# placa_para_insolar_joystick.net
KiCad netlist of a schematic drawn in EAGLE
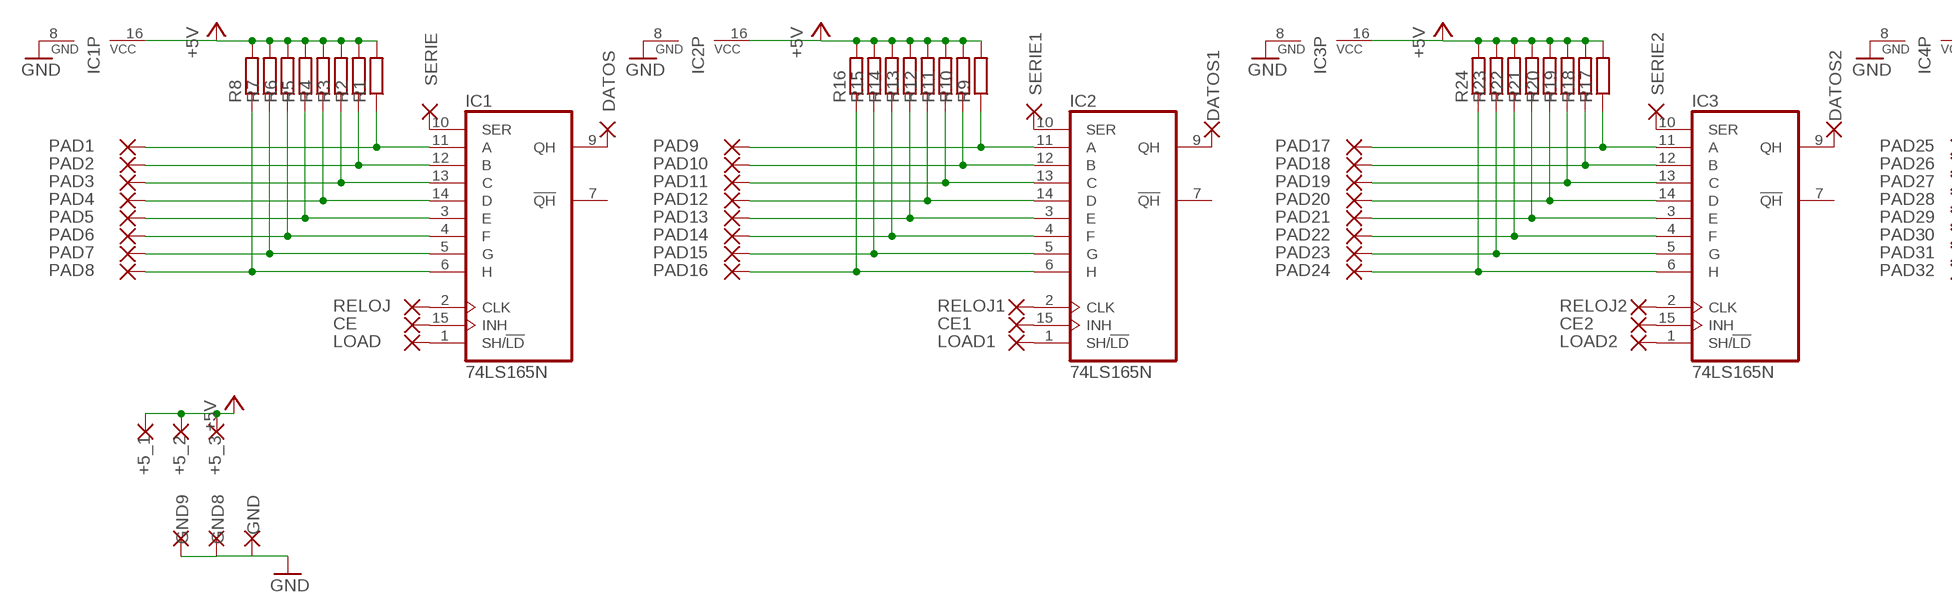
[diagram p0: schematic, sheet 1, part 1 of 2]
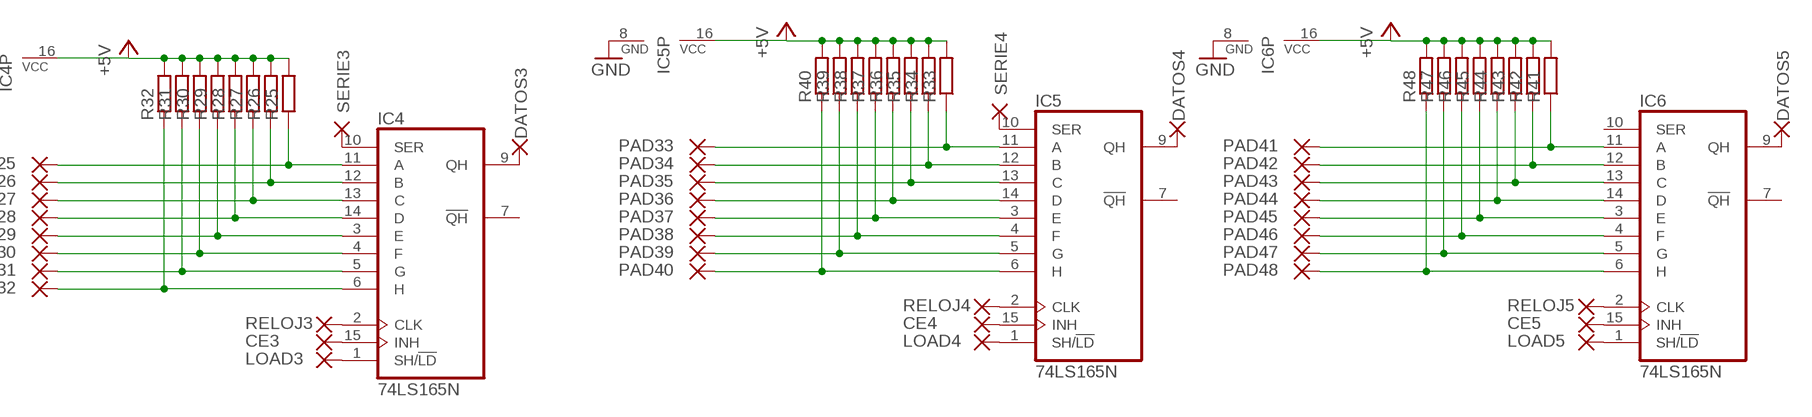
[diagram p1: schematic, sheet 1, part 2 of 2]

(export (version "E")
  (design (tool "Eeschema 10.0.6"))
  (components
    (comp (ref "+5_1")
      (value "WIREPAD2,54/1,0")
      (footprint "eagle-import:2,54_1,0")
      (libsource (lib "eagle-import") (part "WIREPAD2,54/1,0"))
    )
    (comp (ref "+5_2")
      (value "WIREPAD2,54/1,0")
      (footprint "eagle-import:2,54_1,0")
      (libsource (lib "eagle-import") (part "WIREPAD2,54/1,0"))
    )
    (comp (ref "+5_3")
      (value "WIREPAD2,54/1,0")
      (footprint "eagle-import:2,54_1,0")
      (libsource (lib "eagle-import") (part "WIREPAD2,54/1,0"))
    )
    (comp (ref "CE")
      (value "WIREPAD2,54/1,0")
      (footprint "eagle-import:2,54_1,0")
      (libsource (lib "eagle-import") (part "WIREPAD2,54/1,0"))
    )
    (comp (ref "CE1")
      (value "WIREPAD2,54/1,0")
      (footprint "eagle-import:2,54_1,0")
      (libsource (lib "eagle-import") (part "WIREPAD2,54/1,0"))
    )
    (comp (ref "CE2")
      (value "WIREPAD2,54/1,0")
      (footprint "eagle-import:2,54_1,0")
      (libsource (lib "eagle-import") (part "WIREPAD2,54/1,0"))
    )
    (comp (ref "CE3")
      (value "WIREPAD2,54/1,0")
      (footprint "eagle-import:2,54_1,0")
      (libsource (lib "eagle-import") (part "WIREPAD2,54/1,0"))
    )
    (comp (ref "CE4")
      (value "WIREPAD2,54/1,0")
      (footprint "eagle-import:2,54_1,0")
      (libsource (lib "eagle-import") (part "WIREPAD2,54/1,0"))
    )
    (comp (ref "CE5")
      (value "WIREPAD2,54/1,0")
      (footprint "eagle-import:2,54_1,0")
      (libsource (lib "eagle-import") (part "WIREPAD2,54/1,0"))
    )
    (comp (ref "DATOS")
      (value "WIREPAD2,54/1,0")
      (footprint "eagle-import:2,54_1,0")
      (libsource (lib "eagle-import") (part "WIREPAD2,54/1,0"))
    )
    (comp (ref "DATOS1")
      (value "WIREPAD2,54/1,0")
      (footprint "eagle-import:2,54_1,0")
      (libsource (lib "eagle-import") (part "WIREPAD2,54/1,0"))
    )
    (comp (ref "DATOS2")
      (value "WIREPAD2,54/1,0")
      (footprint "eagle-import:2,54_1,0")
      (libsource (lib "eagle-import") (part "WIREPAD2,54/1,0"))
    )
    (comp (ref "DATOS3")
      (value "WIREPAD2,54/1,0")
      (footprint "eagle-import:2,54_1,0")
      (libsource (lib "eagle-import") (part "WIREPAD2,54/1,0"))
    )
    (comp (ref "DATOS4")
      (value "WIREPAD2,54/1,0")
      (footprint "eagle-import:2,54_1,0")
      (libsource (lib "eagle-import") (part "WIREPAD2,54/1,0"))
    )
    (comp (ref "DATOS5")
      (value "WIREPAD2,54/1,0")
      (footprint "eagle-import:2,54_1,0")
      (libsource (lib "eagle-import") (part "WIREPAD2,54/1,0"))
    )
    (comp (ref "GND")
      (value "WIREPAD2,54/1,0")
      (footprint "eagle-import:2,54_1,0")
      (libsource (lib "eagle-import") (part "WIREPAD2,54/1,0"))
    )
    (comp (ref "GND8")
      (value "WIREPAD2,54/1,0")
      (footprint "eagle-import:2,54_1,0")
      (libsource (lib "eagle-import") (part "WIREPAD2,54/1,0"))
    )
    (comp (ref "GND9")
      (value "WIREPAD2,54/1,0")
      (footprint "eagle-import:2,54_1,0")
      (libsource (lib "eagle-import") (part "WIREPAD2,54/1,0"))
    )
    (comp (ref "IC1")
      (value "74LS165N")
      (footprint "eagle-import:DIL16")
      (libsource (lib "eagle-import") (part "74165NLS"))
    )
    (comp (ref "IC2")
      (value "74LS165N")
      (footprint "eagle-import:DIL16")
      (libsource (lib "eagle-import") (part "74165NLS"))
    )
    (comp (ref "IC3")
      (value "74LS165N")
      (footprint "eagle-import:DIL16")
      (libsource (lib "eagle-import") (part "74165NLS"))
    )
    (comp (ref "IC4")
      (value "74LS165N")
      (footprint "eagle-import:DIL16")
      (libsource (lib "eagle-import") (part "74165NLS"))
    )
    (comp (ref "IC5")
      (value "74LS165N")
      (footprint "eagle-import:DIL16")
      (libsource (lib "eagle-import") (part "74165NLS"))
    )
    (comp (ref "IC6")
      (value "74LS165N")
      (footprint "eagle-import:DIL16")
      (libsource (lib "eagle-import") (part "74165NLS"))
    )
    (comp (ref "LOAD")
      (value "WIREPAD2,54/1,0")
      (footprint "eagle-import:2,54_1,0")
      (libsource (lib "eagle-import") (part "WIREPAD2,54/1,0"))
    )
    (comp (ref "LOAD1")
      (value "WIREPAD2,54/1,0")
      (footprint "eagle-import:2,54_1,0")
      (libsource (lib "eagle-import") (part "WIREPAD2,54/1,0"))
    )
    (comp (ref "LOAD2")
      (value "WIREPAD2,54/1,0")
      (footprint "eagle-import:2,54_1,0")
      (libsource (lib "eagle-import") (part "WIREPAD2,54/1,0"))
    )
    (comp (ref "LOAD3")
      (value "WIREPAD2,54/1,0")
      (footprint "eagle-import:2,54_1,0")
      (libsource (lib "eagle-import") (part "WIREPAD2,54/1,0"))
    )
    (comp (ref "LOAD4")
      (value "WIREPAD2,54/1,0")
      (footprint "eagle-import:2,54_1,0")
      (libsource (lib "eagle-import") (part "WIREPAD2,54/1,0"))
    )
    (comp (ref "LOAD5")
      (value "WIREPAD2,54/1,0")
      (footprint "eagle-import:2,54_1,0")
      (libsource (lib "eagle-import") (part "WIREPAD2,54/1,0"))
    )
    (comp (ref "PAD1")
      (value "WIREPAD2,54/1,0")
      (footprint "eagle-import:2,54_1,0")
      (libsource (lib "eagle-import") (part "WIREPAD2,54/1,0"))
    )
    (comp (ref "PAD2")
      (value "WIREPAD2,54/1,0")
      (footprint "eagle-import:2,54_1,0")
      (libsource (lib "eagle-import") (part "WIREPAD2,54/1,0"))
    )
    (comp (ref "PAD3")
      (value "WIREPAD2,54/1,0")
      (footprint "eagle-import:2,54_1,0")
      (libsource (lib "eagle-import") (part "WIREPAD2,54/1,0"))
    )
    (comp (ref "PAD4")
      (value "WIREPAD2,54/1,0")
      (footprint "eagle-import:2,54_1,0")
      (libsource (lib "eagle-import") (part "WIREPAD2,54/1,0"))
    )
    (comp (ref "PAD5")
      (value "WIREPAD2,54/1,0")
      (footprint "eagle-import:2,54_1,0")
      (libsource (lib "eagle-import") (part "WIREPAD2,54/1,0"))
    )
    (comp (ref "PAD6")
      (value "WIREPAD2,54/1,0")
      (footprint "eagle-import:2,54_1,0")
      (libsource (lib "eagle-import") (part "WIREPAD2,54/1,0"))
    )
    (comp (ref "PAD7")
      (value "WIREPAD2,54/1,0")
      (footprint "eagle-import:2,54_1,0")
      (libsource (lib "eagle-import") (part "WIREPAD2,54/1,0"))
    )
    (comp (ref "PAD8")
      (value "WIREPAD2,54/1,0")
      (footprint "eagle-import:2,54_1,0")
      (libsource (lib "eagle-import") (part "WIREPAD2,54/1,0"))
    )
    (comp (ref "PAD9")
      (value "WIREPAD2,54/1,0")
      (footprint "eagle-import:2,54_1,0")
      (libsource (lib "eagle-import") (part "WIREPAD2,54/1,0"))
    )
    (comp (ref "PAD10")
      (value "WIREPAD2,54/1,0")
      (footprint "eagle-import:2,54_1,0")
      (libsource (lib "eagle-import") (part "WIREPAD2,54/1,0"))
    )
    (comp (ref "PAD11")
      (value "WIREPAD2,54/1,0")
      (footprint "eagle-import:2,54_1,0")
      (libsource (lib "eagle-import") (part "WIREPAD2,54/1,0"))
    )
    (comp (ref "PAD12")
      (value "WIREPAD2,54/1,0")
      (footprint "eagle-import:2,54_1,0")
      (libsource (lib "eagle-import") (part "WIREPAD2,54/1,0"))
    )
    (comp (ref "PAD13")
      (value "WIREPAD2,54/1,0")
      (footprint "eagle-import:2,54_1,0")
      (libsource (lib "eagle-import") (part "WIREPAD2,54/1,0"))
    )
    (comp (ref "PAD14")
      (value "WIREPAD2,54/1,0")
      (footprint "eagle-import:2,54_1,0")
      (libsource (lib "eagle-import") (part "WIREPAD2,54/1,0"))
    )
    (comp (ref "PAD15")
      (value "WIREPAD2,54/1,0")
      (footprint "eagle-import:2,54_1,0")
      (libsource (lib "eagle-import") (part "WIREPAD2,54/1,0"))
    )
    (comp (ref "PAD16")
      (value "WIREPAD2,54/1,0")
      (footprint "eagle-import:2,54_1,0")
      (libsource (lib "eagle-import") (part "WIREPAD2,54/1,0"))
    )
    (comp (ref "PAD17")
      (value "WIREPAD2,54/1,0")
      (footprint "eagle-import:2,54_1,0")
      (libsource (lib "eagle-import") (part "WIREPAD2,54/1,0"))
    )
    (comp (ref "PAD18")
      (value "WIREPAD2,54/1,0")
      (footprint "eagle-import:2,54_1,0")
      (libsource (lib "eagle-import") (part "WIREPAD2,54/1,0"))
    )
    (comp (ref "PAD19")
      (value "WIREPAD2,54/1,0")
      (footprint "eagle-import:2,54_1,0")
      (libsource (lib "eagle-import") (part "WIREPAD2,54/1,0"))
    )
    (comp (ref "PAD20")
      (value "WIREPAD2,54/1,0")
      (footprint "eagle-import:2,54_1,0")
      (libsource (lib "eagle-import") (part "WIREPAD2,54/1,0"))
    )
    (comp (ref "PAD21")
      (value "WIREPAD2,54/1,0")
      (footprint "eagle-import:2,54_1,0")
      (libsource (lib "eagle-import") (part "WIREPAD2,54/1,0"))
    )
    (comp (ref "PAD22")
      (value "WIREPAD2,54/1,0")
      (footprint "eagle-import:2,54_1,0")
      (libsource (lib "eagle-import") (part "WIREPAD2,54/1,0"))
    )
    (comp (ref "PAD23")
      (value "WIREPAD2,54/1,0")
      (footprint "eagle-import:2,54_1,0")
      (libsource (lib "eagle-import") (part "WIREPAD2,54/1,0"))
    )
    (comp (ref "PAD24")
      (value "WIREPAD2,54/1,0")
      (footprint "eagle-import:2,54_1,0")
      (libsource (lib "eagle-import") (part "WIREPAD2,54/1,0"))
    )
    (comp (ref "PAD25")
      (value "WIREPAD2,54/1,0")
      (footprint "eagle-import:2,54_1,0")
      (libsource (lib "eagle-import") (part "WIREPAD2,54/1,0"))
    )
    (comp (ref "PAD26")
      (value "WIREPAD2,54/1,0")
      (footprint "eagle-import:2,54_1,0")
      (libsource (lib "eagle-import") (part "WIREPAD2,54/1,0"))
    )
    (comp (ref "PAD27")
      (value "WIREPAD2,54/1,0")
      (footprint "eagle-import:2,54_1,0")
      (libsource (lib "eagle-import") (part "WIREPAD2,54/1,0"))
    )
    (comp (ref "PAD28")
      (value "WIREPAD2,54/1,0")
      (footprint "eagle-import:2,54_1,0")
      (libsource (lib "eagle-import") (part "WIREPAD2,54/1,0"))
    )
    (comp (ref "PAD29")
      (value "WIREPAD2,54/1,0")
      (footprint "eagle-import:2,54_1,0")
      (libsource (lib "eagle-import") (part "WIREPAD2,54/1,0"))
    )
    (comp (ref "PAD30")
      (value "WIREPAD2,54/1,0")
      (footprint "eagle-import:2,54_1,0")
      (libsource (lib "eagle-import") (part "WIREPAD2,54/1,0"))
    )
    (comp (ref "PAD31")
      (value "WIREPAD2,54/1,0")
      (footprint "eagle-import:2,54_1,0")
      (libsource (lib "eagle-import") (part "WIREPAD2,54/1,0"))
    )
    (comp (ref "PAD32")
      (value "WIREPAD2,54/1,0")
      (footprint "eagle-import:2,54_1,0")
      (libsource (lib "eagle-import") (part "WIREPAD2,54/1,0"))
    )
    (comp (ref "PAD33")
      (value "WIREPAD2,54/1,0")
      (footprint "eagle-import:2,54_1,0")
      (libsource (lib "eagle-import") (part "WIREPAD2,54/1,0"))
    )
    (comp (ref "PAD34")
      (value "WIREPAD2,54/1,0")
      (footprint "eagle-import:2,54_1,0")
      (libsource (lib "eagle-import") (part "WIREPAD2,54/1,0"))
    )
    (comp (ref "PAD35")
      (value "WIREPAD2,54/1,0")
      (footprint "eagle-import:2,54_1,0")
      (libsource (lib "eagle-import") (part "WIREPAD2,54/1,0"))
    )
    (comp (ref "PAD36")
      (value "WIREPAD2,54/1,0")
      (footprint "eagle-import:2,54_1,0")
      (libsource (lib "eagle-import") (part "WIREPAD2,54/1,0"))
    )
    (comp (ref "PAD37")
      (value "WIREPAD2,54/1,0")
      (footprint "eagle-import:2,54_1,0")
      (libsource (lib "eagle-import") (part "WIREPAD2,54/1,0"))
    )
    (comp (ref "PAD38")
      (value "WIREPAD2,54/1,0")
      (footprint "eagle-import:2,54_1,0")
      (libsource (lib "eagle-import") (part "WIREPAD2,54/1,0"))
    )
    (comp (ref "PAD39")
      (value "WIREPAD2,54/1,0")
      (footprint "eagle-import:2,54_1,0")
      (libsource (lib "eagle-import") (part "WIREPAD2,54/1,0"))
    )
    (comp (ref "PAD40")
      (value "WIREPAD2,54/1,0")
      (footprint "eagle-import:2,54_1,0")
      (libsource (lib "eagle-import") (part "WIREPAD2,54/1,0"))
    )
    (comp (ref "PAD41")
      (value "WIREPAD2,54/1,0")
      (footprint "eagle-import:2,54_1,0")
      (libsource (lib "eagle-import") (part "WIREPAD2,54/1,0"))
    )
    (comp (ref "PAD42")
      (value "WIREPAD2,54/1,0")
      (footprint "eagle-import:2,54_1,0")
      (libsource (lib "eagle-import") (part "WIREPAD2,54/1,0"))
    )
    (comp (ref "PAD43")
      (value "WIREPAD2,54/1,0")
      (footprint "eagle-import:2,54_1,0")
      (libsource (lib "eagle-import") (part "WIREPAD2,54/1,0"))
    )
    (comp (ref "PAD44")
      (value "WIREPAD2,54/1,0")
      (footprint "eagle-import:2,54_1,0")
      (libsource (lib "eagle-import") (part "WIREPAD2,54/1,0"))
    )
    (comp (ref "PAD45")
      (value "WIREPAD2,54/1,0")
      (footprint "eagle-import:2,54_1,0")
      (libsource (lib "eagle-import") (part "WIREPAD2,54/1,0"))
    )
    (comp (ref "PAD46")
      (value "WIREPAD2,54/1,0")
      (footprint "eagle-import:2,54_1,0")
      (libsource (lib "eagle-import") (part "WIREPAD2,54/1,0"))
    )
    (comp (ref "PAD47")
      (value "WIREPAD2,54/1,0")
      (footprint "eagle-import:2,54_1,0")
      (libsource (lib "eagle-import") (part "WIREPAD2,54/1,0"))
    )
    (comp (ref "PAD48")
      (value "WIREPAD2,54/1,0")
      (footprint "eagle-import:2,54_1,0")
      (libsource (lib "eagle-import") (part "WIREPAD2,54/1,0"))
    )
    (comp (ref "R1")
      (value "R-EU_0204/7")
      (footprint "eagle-import:0204_7")
      (libsource (lib "eagle-import") (part "R-EU_0204/7"))
    )
    (comp (ref "R2")
      (value "R-EU_0204/7")
      (footprint "eagle-import:0204_7")
      (libsource (lib "eagle-import") (part "R-EU_0204/7"))
    )
    (comp (ref "R3")
      (value "R-EU_0204/7")
      (footprint "eagle-import:0204_7")
      (libsource (lib "eagle-import") (part "R-EU_0204/7"))
    )
    (comp (ref "R4")
      (value "R-EU_0204/7")
      (footprint "eagle-import:0204_7")
      (libsource (lib "eagle-import") (part "R-EU_0204/7"))
    )
    (comp (ref "R5")
      (value "R-EU_0204/7")
      (footprint "eagle-import:0204_7")
      (libsource (lib "eagle-import") (part "R-EU_0204/7"))
    )
    (comp (ref "R6")
      (value "R-EU_0204/7")
      (footprint "eagle-import:0204_7")
      (libsource (lib "eagle-import") (part "R-EU_0204/7"))
    )
    (comp (ref "R7")
      (value "R-EU_0204/7")
      (footprint "eagle-import:0204_7")
      (libsource (lib "eagle-import") (part "R-EU_0204/7"))
    )
    (comp (ref "R8")
      (value "R-EU_0204/7")
      (footprint "eagle-import:0204_7")
      (libsource (lib "eagle-import") (part "R-EU_0204/7"))
    )
    (comp (ref "R9")
      (value "R-EU_0204/7")
      (footprint "eagle-import:0204_7")
      (libsource (lib "eagle-import") (part "R-EU_0204/7"))
    )
    (comp (ref "R10")
      (value "R-EU_0204/7")
      (footprint "eagle-import:0204_7")
      (libsource (lib "eagle-import") (part "R-EU_0204/7"))
    )
    (comp (ref "R11")
      (value "R-EU_0204/7")
      (footprint "eagle-import:0204_7")
      (libsource (lib "eagle-import") (part "R-EU_0204/7"))
    )
    (comp (ref "R12")
      (value "R-EU_0204/7")
      (footprint "eagle-import:0204_7")
      (libsource (lib "eagle-import") (part "R-EU_0204/7"))
    )
    (comp (ref "R13")
      (value "R-EU_0204/7")
      (footprint "eagle-import:0204_7")
      (libsource (lib "eagle-import") (part "R-EU_0204/7"))
    )
    (comp (ref "R14")
      (value "R-EU_0204/7")
      (footprint "eagle-import:0204_7")
      (libsource (lib "eagle-import") (part "R-EU_0204/7"))
    )
    (comp (ref "R15")
      (value "R-EU_0204/7")
      (footprint "eagle-import:0204_7")
      (libsource (lib "eagle-import") (part "R-EU_0204/7"))
    )
    (comp (ref "R16")
      (value "R-EU_0204/7")
      (footprint "eagle-import:0204_7")
      (libsource (lib "eagle-import") (part "R-EU_0204/7"))
    )
    (comp (ref "R17")
      (value "R-EU_0204/7")
      (footprint "eagle-import:0204_7")
      (libsource (lib "eagle-import") (part "R-EU_0204/7"))
    )
    (comp (ref "R18")
      (value "R-EU_0204/7")
      (footprint "eagle-import:0204_7")
      (libsource (lib "eagle-import") (part "R-EU_0204/7"))
    )
    (comp (ref "R19")
      (value "R-EU_0204/7")
      (footprint "eagle-import:0204_7")
      (libsource (lib "eagle-import") (part "R-EU_0204/7"))
    )
    (comp (ref "R20")
      (value "R-EU_0204/7")
      (footprint "eagle-import:0204_7")
      (libsource (lib "eagle-import") (part "R-EU_0204/7"))
    )
    (comp (ref "R21")
      (value "R-EU_0204/7")
      (footprint "eagle-import:0204_7")
      (libsource (lib "eagle-import") (part "R-EU_0204/7"))
    )
    (comp (ref "R22")
      (value "R-EU_0204/7")
      (footprint "eagle-import:0204_7")
      (libsource (lib "eagle-import") (part "R-EU_0204/7"))
    )
    (comp (ref "R23")
      (value "R-EU_0204/7")
      (footprint "eagle-import:0204_7")
      (libsource (lib "eagle-import") (part "R-EU_0204/7"))
    )
    (comp (ref "R24")
      (value "R-EU_0204/7")
      (footprint "eagle-import:0204_7")
      (libsource (lib "eagle-import") (part "R-EU_0204/7"))
    )
    (comp (ref "R25")
      (value "R-EU_0204/7")
      (footprint "eagle-import:0204_7")
      (libsource (lib "eagle-import") (part "R-EU_0204/7"))
    )
    (comp (ref "R26")
      (value "R-EU_0204/7")
      (footprint "eagle-import:0204_7")
      (libsource (lib "eagle-import") (part "R-EU_0204/7"))
    )
    (comp (ref "R27")
      (value "R-EU_0204/7")
      (footprint "eagle-import:0204_7")
      (libsource (lib "eagle-import") (part "R-EU_0204/7"))
    )
    (comp (ref "R28")
      (value "R-EU_0204/7")
      (footprint "eagle-import:0204_7")
      (libsource (lib "eagle-import") (part "R-EU_0204/7"))
    )
    (comp (ref "R29")
      (value "R-EU_0204/7")
      (footprint "eagle-import:0204_7")
      (libsource (lib "eagle-import") (part "R-EU_0204/7"))
    )
    (comp (ref "R30")
      (value "R-EU_0204/7")
      (footprint "eagle-import:0204_7")
      (libsource (lib "eagle-import") (part "R-EU_0204/7"))
    )
    (comp (ref "R31")
      (value "R-EU_0204/7")
      (footprint "eagle-import:0204_7")
      (libsource (lib "eagle-import") (part "R-EU_0204/7"))
    )
    (comp (ref "R32")
      (value "R-EU_0204/7")
      (footprint "eagle-import:0204_7")
      (libsource (lib "eagle-import") (part "R-EU_0204/7"))
    )
    (comp (ref "R33")
      (value "R-EU_0204/7")
      (footprint "eagle-import:0204_7")
      (libsource (lib "eagle-import") (part "R-EU_0204/7"))
    )
    (comp (ref "R34")
      (value "R-EU_0204/7")
      (footprint "eagle-import:0204_7")
      (libsource (lib "eagle-import") (part "R-EU_0204/7"))
    )
    (comp (ref "R35")
      (value "R-EU_0204/7")
      (footprint "eagle-import:0204_7")
      (libsource (lib "eagle-import") (part "R-EU_0204/7"))
    )
    (comp (ref "R36")
      (value "R-EU_0204/7")
      (footprint "eagle-import:0204_7")
      (libsource (lib "eagle-import") (part "R-EU_0204/7"))
    )
    (comp (ref "R37")
      (value "R-EU_0204/7")
      (footprint "eagle-import:0204_7")
      (libsource (lib "eagle-import") (part "R-EU_0204/7"))
    )
    (comp (ref "R38")
      (value "R-EU_0204/7")
      (footprint "eagle-import:0204_7")
      (libsource (lib "eagle-import") (part "R-EU_0204/7"))
    )
    (comp (ref "R39")
      (value "R-EU_0204/7")
      (footprint "eagle-import:0204_7")
      (libsource (lib "eagle-import") (part "R-EU_0204/7"))
    )
    (comp (ref "R40")
      (value "R-EU_0204/7")
      (footprint "eagle-import:0204_7")
      (libsource (lib "eagle-import") (part "R-EU_0204/7"))
    )
    (comp (ref "R41")
      (value "R-EU_0204/7")
      (footprint "eagle-import:0204_7")
      (libsource (lib "eagle-import") (part "R-EU_0204/7"))
    )
    (comp (ref "R42")
      (value "R-EU_0204/7")
      (footprint "eagle-import:0204_7")
      (libsource (lib "eagle-import") (part "R-EU_0204/7"))
    )
    (comp (ref "R43")
      (value "R-EU_0204/7")
      (footprint "eagle-import:0204_7")
      (libsource (lib "eagle-import") (part "R-EU_0204/7"))
    )
    (comp (ref "R44")
      (value "R-EU_0204/7")
      (footprint "eagle-import:0204_7")
      (libsource (lib "eagle-import") (part "R-EU_0204/7"))
    )
    (comp (ref "R45")
      (value "R-EU_0204/7")
      (footprint "eagle-import:0204_7")
      (libsource (lib "eagle-import") (part "R-EU_0204/7"))
    )
    (comp (ref "R46")
      (value "R-EU_0204/7")
      (footprint "eagle-import:0204_7")
      (libsource (lib "eagle-import") (part "R-EU_0204/7"))
    )
    (comp (ref "R47")
      (value "R-EU_0204/7")
      (footprint "eagle-import:0204_7")
      (libsource (lib "eagle-import") (part "R-EU_0204/7"))
    )
    (comp (ref "R48")
      (value "R-EU_0204/7")
      (footprint "eagle-import:0204_7")
      (libsource (lib "eagle-import") (part "R-EU_0204/7"))
    )
    (comp (ref "RELOJ")
      (value "WIREPAD2,54/1,0")
      (footprint "eagle-import:2,54_1,0")
      (libsource (lib "eagle-import") (part "WIREPAD2,54/1,0"))
    )
    (comp (ref "RELOJ1")
      (value "WIREPAD2,54/1,0")
      (footprint "eagle-import:2,54_1,0")
      (libsource (lib "eagle-import") (part "WIREPAD2,54/1,0"))
    )
    (comp (ref "RELOJ2")
      (value "WIREPAD2,54/1,0")
      (footprint "eagle-import:2,54_1,0")
      (libsource (lib "eagle-import") (part "WIREPAD2,54/1,0"))
    )
    (comp (ref "RELOJ3")
      (value "WIREPAD2,54/1,0")
      (footprint "eagle-import:2,54_1,0")
      (libsource (lib "eagle-import") (part "WIREPAD2,54/1,0"))
    )
    (comp (ref "RELOJ4")
      (value "WIREPAD2,54/1,0")
      (footprint "eagle-import:2,54_1,0")
      (libsource (lib "eagle-import") (part "WIREPAD2,54/1,0"))
    )
    (comp (ref "RELOJ5")
      (value "WIREPAD2,54/1,0")
      (footprint "eagle-import:2,54_1,0")
      (libsource (lib "eagle-import") (part "WIREPAD2,54/1,0"))
    )
    (comp (ref "SERIE")
      (value "WIREPAD2,54/1,0")
      (footprint "eagle-import:2,54_1,0")
      (libsource (lib "eagle-import") (part "WIREPAD2,54/1,0"))
    )
    (comp (ref "SERIE1")
      (value "WIREPAD2,54/1,0")
      (footprint "eagle-import:2,54_1,0")
      (libsource (lib "eagle-import") (part "WIREPAD2,54/1,0"))
    )
    (comp (ref "SERIE2")
      (value "WIREPAD2,54/1,0")
      (footprint "eagle-import:2,54_1,0")
      (libsource (lib "eagle-import") (part "WIREPAD2,54/1,0"))
    )
    (comp (ref "SERIE3")
      (value "WIREPAD2,54/1,0")
      (footprint "eagle-import:2,54_1,0")
      (libsource (lib "eagle-import") (part "WIREPAD2,54/1,0"))
    )
    (comp (ref "SERIE4")
      (value "WIREPAD2,54/1,0")
      (footprint "eagle-import:2,54_1,0")
      (libsource (lib "eagle-import") (part "WIREPAD2,54/1,0"))
    )
  )
  (nets
    (net (code "1") (name "+5V") (class "Default")
      (node (ref "+5_1") (pin "1") (pinfunction "P_1") (pintype "passive"))
      (node (ref "+5_2") (pin "1") (pinfunction "P_1") (pintype "passive"))
      (node (ref "+5_3") (pin "1") (pinfunction "P_1") (pintype "passive"))
      (node (ref "IC1") (pin "16") (pinfunction "VCC_16") (pintype "power_in"))
      (node (ref "IC2") (pin "16") (pinfunction "VCC_16") (pintype "power_in"))
      (node (ref "IC3") (pin "16") (pinfunction "VCC_16") (pintype "power_in"))
      (node (ref "IC4") (pin "16") (pinfunction "VCC_16") (pintype "power_in"))
      (node (ref "IC5") (pin "16") (pinfunction "VCC_16") (pintype "power_in"))
      (node (ref "IC6") (pin "16") (pinfunction "VCC_16") (pintype "power_in"))
      (node (ref "R1") (pin "2") (pinfunction "2_2") (pintype "passive"))
      (node (ref "R10") (pin "2") (pinfunction "2_2") (pintype "passive"))
      (node (ref "R11") (pin "2") (pinfunction "2_2") (pintype "passive"))
      (node (ref "R12") (pin "2") (pinfunction "2_2") (pintype "passive"))
      (node (ref "R13") (pin "2") (pinfunction "2_2") (pintype "passive"))
      (node (ref "R14") (pin "2") (pinfunction "2_2") (pintype "passive"))
      (node (ref "R15") (pin "2") (pinfunction "2_2") (pintype "passive"))
      (node (ref "R16") (pin "2") (pinfunction "2_2") (pintype "passive"))
      (node (ref "R17") (pin "2") (pinfunction "2_2") (pintype "passive"))
      (node (ref "R18") (pin "2") (pinfunction "2_2") (pintype "passive"))
      (node (ref "R19") (pin "2") (pinfunction "2_2") (pintype "passive"))
      (node (ref "R2") (pin "2") (pinfunction "2_2") (pintype "passive"))
      (node (ref "R20") (pin "2") (pinfunction "2_2") (pintype "passive"))
      (node (ref "R21") (pin "2") (pinfunction "2_2") (pintype "passive"))
      (node (ref "R22") (pin "2") (pinfunction "2_2") (pintype "passive"))
      (node (ref "R23") (pin "2") (pinfunction "2_2") (pintype "passive"))
      (node (ref "R24") (pin "2") (pinfunction "2_2") (pintype "passive"))
      (node (ref "R25") (pin "2") (pinfunction "2_2") (pintype "passive"))
      (node (ref "R26") (pin "2") (pinfunction "2_2") (pintype "passive"))
      (node (ref "R27") (pin "2") (pinfunction "2_2") (pintype "passive"))
      (node (ref "R28") (pin "2") (pinfunction "2_2") (pintype "passive"))
      (node (ref "R29") (pin "2") (pinfunction "2_2") (pintype "passive"))
      (node (ref "R3") (pin "2") (pinfunction "2_2") (pintype "passive"))
      (node (ref "R30") (pin "2") (pinfunction "2_2") (pintype "passive"))
      (node (ref "R31") (pin "2") (pinfunction "2_2") (pintype "passive"))
      (node (ref "R32") (pin "2") (pinfunction "2_2") (pintype "passive"))
      (node (ref "R33") (pin "2") (pinfunction "2_2") (pintype "passive"))
      (node (ref "R34") (pin "2") (pinfunction "2_2") (pintype "passive"))
      (node (ref "R35") (pin "2") (pinfunction "2_2") (pintype "passive"))
      (node (ref "R36") (pin "2") (pinfunction "2_2") (pintype "passive"))
      (node (ref "R37") (pin "2") (pinfunction "2_2") (pintype "passive"))
      (node (ref "R38") (pin "2") (pinfunction "2_2") (pintype "passive"))
      (node (ref "R39") (pin "2") (pinfunction "2_2") (pintype "passive"))
      (node (ref "R4") (pin "2") (pinfunction "2_2") (pintype "passive"))
      (node (ref "R40") (pin "2") (pinfunction "2_2") (pintype "passive"))
      (node (ref "R41") (pin "2") (pinfunction "2_2") (pintype "passive"))
      (node (ref "R42") (pin "2") (pinfunction "2_2") (pintype "passive"))
      (node (ref "R43") (pin "2") (pinfunction "2_2") (pintype "passive"))
      (node (ref "R44") (pin "2") (pinfunction "2_2") (pintype "passive"))
      (node (ref "R45") (pin "2") (pinfunction "2_2") (pintype "passive"))
      (node (ref "R46") (pin "2") (pinfunction "2_2") (pintype "passive"))
      (node (ref "R47") (pin "2") (pinfunction "2_2") (pintype "passive"))
      (node (ref "R48") (pin "2") (pinfunction "2_2") (pintype "passive"))
      (node (ref "R5") (pin "2") (pinfunction "2_2") (pintype "passive"))
      (node (ref "R6") (pin "2") (pinfunction "2_2") (pintype "passive"))
      (node (ref "R7") (pin "2") (pinfunction "2_2") (pintype "passive"))
      (node (ref "R8") (pin "2") (pinfunction "2_2") (pintype "passive"))
      (node (ref "R9") (pin "2") (pinfunction "2_2") (pintype "passive"))
    )
    (net (code "2") (name "GND") (class "Default")
      (node (ref "GND") (pin "1") (pinfunction "P_1") (pintype "passive"))
      (node (ref "GND8") (pin "1") (pinfunction "P_1") (pintype "passive"))
      (node (ref "GND9") (pin "1") (pinfunction "P_1") (pintype "passive"))
      (node (ref "IC1") (pin "8") (pinfunction "GND_8") (pintype "power_in"))
      (node (ref "IC2") (pin "8") (pinfunction "GND_8") (pintype "power_in"))
      (node (ref "IC3") (pin "8") (pinfunction "GND_8") (pintype "power_in"))
      (node (ref "IC4") (pin "8") (pinfunction "GND_8") (pintype "power_in"))
      (node (ref "IC5") (pin "8") (pinfunction "GND_8") (pintype "power_in"))
      (node (ref "IC6") (pin "8") (pinfunction "GND_8") (pintype "power_in"))
    )
    (net (code "3") (name "Net-(CE-P)") (class "Default")
      (node (ref "CE") (pin "1") (pinfunction "P_1") (pintype "passive"))
      (node (ref "IC1") (pin "15") (pinfunction "INH_15") (pintype "input"))
    )
    (net (code "4") (name "Net-(CE1-P)") (class "Default")
      (node (ref "CE1") (pin "1") (pinfunction "P_1") (pintype "passive"))
      (node (ref "IC2") (pin "15") (pinfunction "INH_15") (pintype "input"))
    )
    (net (code "5") (name "Net-(CE2-P)") (class "Default")
      (node (ref "CE2") (pin "1") (pinfunction "P_1") (pintype "passive"))
      (node (ref "IC3") (pin "15") (pinfunction "INH_15") (pintype "input"))
    )
    (net (code "6") (name "Net-(CE3-P)") (class "Default")
      (node (ref "CE3") (pin "1") (pinfunction "P_1") (pintype "passive"))
      (node (ref "IC4") (pin "15") (pinfunction "INH_15") (pintype "input"))
    )
    (net (code "7") (name "Net-(CE4-P)") (class "Default")
      (node (ref "CE4") (pin "1") (pinfunction "P_1") (pintype "passive"))
      (node (ref "IC5") (pin "15") (pinfunction "INH_15") (pintype "input"))
    )
    (net (code "8") (name "Net-(CE5-P)") (class "Default")
      (node (ref "CE5") (pin "1") (pinfunction "P_1") (pintype "passive"))
      (node (ref "IC6") (pin "15") (pinfunction "INH_15") (pintype "input"))
    )
    (net (code "9") (name "Net-(DATOS-P)") (class "Default")
      (node (ref "DATOS") (pin "1") (pinfunction "P_1") (pintype "passive"))
      (node (ref "IC1") (pin "9") (pinfunction "QH_9") (pintype "output"))
    )
    (net (code "10") (name "Net-(DATOS1-P)") (class "Default")
      (node (ref "DATOS1") (pin "1") (pinfunction "P_1") (pintype "passive"))
      (node (ref "IC2") (pin "9") (pinfunction "QH_9") (pintype "output"))
    )
    (net (code "11") (name "Net-(DATOS2-P)") (class "Default")
      (node (ref "DATOS2") (pin "1") (pinfunction "P_1") (pintype "passive"))
      (node (ref "IC3") (pin "9") (pinfunction "QH_9") (pintype "output"))
    )
    (net (code "12") (name "Net-(DATOS3-P)") (class "Default")
      (node (ref "DATOS3") (pin "1") (pinfunction "P_1") (pintype "passive"))
      (node (ref "IC4") (pin "9") (pinfunction "QH_9") (pintype "output"))
    )
    (net (code "13") (name "Net-(DATOS4-P)") (class "Default")
      (node (ref "DATOS4") (pin "1") (pinfunction "P_1") (pintype "passive"))
      (node (ref "IC5") (pin "9") (pinfunction "QH_9") (pintype "output"))
    )
    (net (code "14") (name "Net-(DATOS5-P)") (class "Default")
      (node (ref "DATOS5") (pin "1") (pinfunction "P_1") (pintype "passive"))
      (node (ref "IC6") (pin "9") (pinfunction "QH_9") (pintype "output"))
    )
    (net (code "15") (name "Net-(IC1A-A)") (class "Default")
      (node (ref "IC1") (pin "11") (pinfunction "A_11") (pintype "input"))
      (node (ref "PAD1") (pin "1") (pinfunction "P_1") (pintype "passive"))
      (node (ref "R1") (pin "1") (pinfunction "1_1") (pintype "passive"))
    )
    (net (code "16") (name "Net-(IC1A-B)") (class "Default")
      (node (ref "IC1") (pin "12") (pinfunction "B_12") (pintype "input"))
      (node (ref "PAD2") (pin "1") (pinfunction "P_1") (pintype "passive"))
      (node (ref "R2") (pin "1") (pinfunction "1_1") (pintype "passive"))
    )
    (net (code "17") (name "Net-(IC1A-C)") (class "Default")
      (node (ref "IC1") (pin "13") (pinfunction "C_13") (pintype "input"))
      (node (ref "PAD3") (pin "1") (pinfunction "P_1") (pintype "passive"))
      (node (ref "R3") (pin "1") (pinfunction "1_1") (pintype "passive"))
    )
    (net (code "18") (name "Net-(IC1A-CLK)") (class "Default")
      (node (ref "IC1") (pin "2") (pinfunction "CLK_2") (pintype "input"))
      (node (ref "RELOJ") (pin "1") (pinfunction "P_1") (pintype "passive"))
    )
    (net (code "19") (name "Net-(IC1A-D)") (class "Default")
      (node (ref "IC1") (pin "14") (pinfunction "D_14") (pintype "input"))
      (node (ref "PAD4") (pin "1") (pinfunction "P_1") (pintype "passive"))
      (node (ref "R4") (pin "1") (pinfunction "1_1") (pintype "passive"))
    )
    (net (code "20") (name "Net-(IC1A-E)") (class "Default")
      (node (ref "IC1") (pin "3") (pinfunction "E_3") (pintype "input"))
      (node (ref "PAD5") (pin "1") (pinfunction "P_1") (pintype "passive"))
      (node (ref "R5") (pin "1") (pinfunction "1_1") (pintype "passive"))
    )
    (net (code "21") (name "Net-(IC1A-F)") (class "Default")
      (node (ref "IC1") (pin "4") (pinfunction "F_4") (pintype "input"))
      (node (ref "PAD6") (pin "1") (pinfunction "P_1") (pintype "passive"))
      (node (ref "R6") (pin "1") (pinfunction "1_1") (pintype "passive"))
    )
    (net (code "22") (name "Net-(IC1A-G)") (class "Default")
      (node (ref "IC1") (pin "5") (pinfunction "G_5") (pintype "input"))
      (node (ref "PAD7") (pin "1") (pinfunction "P_1") (pintype "passive"))
      (node (ref "R7") (pin "1") (pinfunction "1_1") (pintype "passive"))
    )
    (net (code "23") (name "Net-(IC1A-H)") (class "Default")
      (node (ref "IC1") (pin "6") (pinfunction "H_6") (pintype "input"))
      (node (ref "PAD8") (pin "1") (pinfunction "P_1") (pintype "passive"))
      (node (ref "R8") (pin "1") (pinfunction "1_1") (pintype "passive"))
    )
    (net (code "24") (name "Net-(IC1A-SER)") (class "Default")
      (node (ref "IC1") (pin "10") (pinfunction "SER_10") (pintype "input"))
      (node (ref "SERIE") (pin "1") (pinfunction "P_1") (pintype "passive"))
    )
    (net (code "25") (name "Net-(IC1A-SH{slash}~{LD})") (class "Default")
      (node (ref "IC1") (pin "1") (pinfunction "SH/~{LD}_1") (pintype "input"))
      (node (ref "LOAD") (pin "1") (pinfunction "P_1") (pintype "passive"))
    )
    (net (code "26") (name "Net-(IC2A-A)") (class "Default")
      (node (ref "IC2") (pin "11") (pinfunction "A_11") (pintype "input"))
      (node (ref "PAD9") (pin "1") (pinfunction "P_1") (pintype "passive"))
      (node (ref "R9") (pin "1") (pinfunction "1_1") (pintype "passive"))
    )
    (net (code "27") (name "Net-(IC2A-B)") (class "Default")
      (node (ref "IC2") (pin "12") (pinfunction "B_12") (pintype "input"))
      (node (ref "PAD10") (pin "1") (pinfunction "P_1") (pintype "passive"))
      (node (ref "R10") (pin "1") (pinfunction "1_1") (pintype "passive"))
    )
    (net (code "28") (name "Net-(IC2A-C)") (class "Default")
      (node (ref "IC2") (pin "13") (pinfunction "C_13") (pintype "input"))
      (node (ref "PAD11") (pin "1") (pinfunction "P_1") (pintype "passive"))
      (node (ref "R11") (pin "1") (pinfunction "1_1") (pintype "passive"))
    )
    (net (code "29") (name "Net-(IC2A-CLK)") (class "Default")
      (node (ref "IC2") (pin "2") (pinfunction "CLK_2") (pintype "input"))
      (node (ref "RELOJ1") (pin "1") (pinfunction "P_1") (pintype "passive"))
    )
    (net (code "30") (name "Net-(IC2A-D)") (class "Default")
      (node (ref "IC2") (pin "14") (pinfunction "D_14") (pintype "input"))
      (node (ref "PAD12") (pin "1") (pinfunction "P_1") (pintype "passive"))
      (node (ref "R12") (pin "1") (pinfunction "1_1") (pintype "passive"))
    )
    (net (code "31") (name "Net-(IC2A-E)") (class "Default")
      (node (ref "IC2") (pin "3") (pinfunction "E_3") (pintype "input"))
      (node (ref "PAD13") (pin "1") (pinfunction "P_1") (pintype "passive"))
      (node (ref "R13") (pin "1") (pinfunction "1_1") (pintype "passive"))
    )
    (net (code "32") (name "Net-(IC2A-F)") (class "Default")
      (node (ref "IC2") (pin "4") (pinfunction "F_4") (pintype "input"))
      (node (ref "PAD14") (pin "1") (pinfunction "P_1") (pintype "passive"))
      (node (ref "R14") (pin "1") (pinfunction "1_1") (pintype "passive"))
    )
    (net (code "33") (name "Net-(IC2A-G)") (class "Default")
      (node (ref "IC2") (pin "5") (pinfunction "G_5") (pintype "input"))
      (node (ref "PAD15") (pin "1") (pinfunction "P_1") (pintype "passive"))
      (node (ref "R15") (pin "1") (pinfunction "1_1") (pintype "passive"))
    )
    (net (code "34") (name "Net-(IC2A-H)") (class "Default")
      (node (ref "IC2") (pin "6") (pinfunction "H_6") (pintype "input"))
      (node (ref "PAD16") (pin "1") (pinfunction "P_1") (pintype "passive"))
      (node (ref "R16") (pin "1") (pinfunction "1_1") (pintype "passive"))
    )
    (net (code "35") (name "Net-(IC2A-SER)") (class "Default")
      (node (ref "IC2") (pin "10") (pinfunction "SER_10") (pintype "input"))
      (node (ref "SERIE1") (pin "1") (pinfunction "P_1") (pintype "passive"))
    )
    (net (code "36") (name "Net-(IC2A-SH{slash}~{LD})") (class "Default")
      (node (ref "IC2") (pin "1") (pinfunction "SH/~{LD}_1") (pintype "input"))
      (node (ref "LOAD1") (pin "1") (pinfunction "P_1") (pintype "passive"))
    )
    (net (code "37") (name "Net-(IC3A-A)") (class "Default")
      (node (ref "IC3") (pin "11") (pinfunction "A_11") (pintype "input"))
      (node (ref "PAD17") (pin "1") (pinfunction "P_1") (pintype "passive"))
      (node (ref "R17") (pin "1") (pinfunction "1_1") (pintype "passive"))
    )
    (net (code "38") (name "Net-(IC3A-B)") (class "Default")
      (node (ref "IC3") (pin "12") (pinfunction "B_12") (pintype "input"))
      (node (ref "PAD18") (pin "1") (pinfunction "P_1") (pintype "passive"))
      (node (ref "R18") (pin "1") (pinfunction "1_1") (pintype "passive"))
    )
    (net (code "39") (name "Net-(IC3A-C)") (class "Default")
      (node (ref "IC3") (pin "13") (pinfunction "C_13") (pintype "input"))
      (node (ref "PAD19") (pin "1") (pinfunction "P_1") (pintype "passive"))
      (node (ref "R19") (pin "1") (pinfunction "1_1") (pintype "passive"))
    )
    (net (code "40") (name "Net-(IC3A-CLK)") (class "Default")
      (node (ref "IC3") (pin "2") (pinfunction "CLK_2") (pintype "input"))
      (node (ref "RELOJ2") (pin "1") (pinfunction "P_1") (pintype "passive"))
    )
    (net (code "41") (name "Net-(IC3A-D)") (class "Default")
      (node (ref "IC3") (pin "14") (pinfunction "D_14") (pintype "input"))
      (node (ref "PAD20") (pin "1") (pinfunction "P_1") (pintype "passive"))
      (node (ref "R20") (pin "1") (pinfunction "1_1") (pintype "passive"))
    )
    (net (code "42") (name "Net-(IC3A-E)") (class "Default")
      (node (ref "IC3") (pin "3") (pinfunction "E_3") (pintype "input"))
      (node (ref "PAD21") (pin "1") (pinfunction "P_1") (pintype "passive"))
      (node (ref "R21") (pin "1") (pinfunction "1_1") (pintype "passive"))
    )
    (net (code "43") (name "Net-(IC3A-F)") (class "Default")
      (node (ref "IC3") (pin "4") (pinfunction "F_4") (pintype "input"))
      (node (ref "PAD22") (pin "1") (pinfunction "P_1") (pintype "passive"))
      (node (ref "R22") (pin "1") (pinfunction "1_1") (pintype "passive"))
    )
    (net (code "44") (name "Net-(IC3A-G)") (class "Default")
      (node (ref "IC3") (pin "5") (pinfunction "G_5") (pintype "input"))
      (node (ref "PAD23") (pin "1") (pinfunction "P_1") (pintype "passive"))
      (node (ref "R23") (pin "1") (pinfunction "1_1") (pintype "passive"))
    )
    (net (code "45") (name "Net-(IC3A-H)") (class "Default")
      (node (ref "IC3") (pin "6") (pinfunction "H_6") (pintype "input"))
      (node (ref "PAD24") (pin "1") (pinfunction "P_1") (pintype "passive"))
      (node (ref "R24") (pin "1") (pinfunction "1_1") (pintype "passive"))
    )
    (net (code "46") (name "Net-(IC3A-SER)") (class "Default")
      (node (ref "IC3") (pin "10") (pinfunction "SER_10") (pintype "input"))
      (node (ref "SERIE2") (pin "1") (pinfunction "P_1") (pintype "passive"))
    )
    (net (code "47") (name "Net-(IC3A-SH{slash}~{LD})") (class "Default")
      (node (ref "IC3") (pin "1") (pinfunction "SH/~{LD}_1") (pintype "input"))
      (node (ref "LOAD2") (pin "1") (pinfunction "P_1") (pintype "passive"))
    )
    (net (code "48") (name "Net-(IC4A-A)") (class "Default")
      (node (ref "IC4") (pin "11") (pinfunction "A_11") (pintype "input"))
      (node (ref "PAD25") (pin "1") (pinfunction "P_1") (pintype "passive"))
      (node (ref "R25") (pin "1") (pinfunction "1_1") (pintype "passive"))
    )
    (net (code "49") (name "Net-(IC4A-B)") (class "Default")
      (node (ref "IC4") (pin "12") (pinfunction "B_12") (pintype "input"))
      (node (ref "PAD26") (pin "1") (pinfunction "P_1") (pintype "passive"))
      (node (ref "R26") (pin "1") (pinfunction "1_1") (pintype "passive"))
    )
    (net (code "50") (name "Net-(IC4A-C)") (class "Default")
      (node (ref "IC4") (pin "13") (pinfunction "C_13") (pintype "input"))
      (node (ref "PAD27") (pin "1") (pinfunction "P_1") (pintype "passive"))
      (node (ref "R27") (pin "1") (pinfunction "1_1") (pintype "passive"))
    )
    (net (code "51") (name "Net-(IC4A-CLK)") (class "Default")
      (node (ref "IC4") (pin "2") (pinfunction "CLK_2") (pintype "input"))
      (node (ref "RELOJ3") (pin "1") (pinfunction "P_1") (pintype "passive"))
    )
    (net (code "52") (name "Net-(IC4A-D)") (class "Default")
      (node (ref "IC4") (pin "14") (pinfunction "D_14") (pintype "input"))
      (node (ref "PAD28") (pin "1") (pinfunction "P_1") (pintype "passive"))
      (node (ref "R28") (pin "1") (pinfunction "1_1") (pintype "passive"))
    )
    (net (code "53") (name "Net-(IC4A-E)") (class "Default")
      (node (ref "IC4") (pin "3") (pinfunction "E_3") (pintype "input"))
      (node (ref "PAD29") (pin "1") (pinfunction "P_1") (pintype "passive"))
      (node (ref "R29") (pin "1") (pinfunction "1_1") (pintype "passive"))
    )
    (net (code "54") (name "Net-(IC4A-F)") (class "Default")
      (node (ref "IC4") (pin "4") (pinfunction "F_4") (pintype "input"))
      (node (ref "PAD30") (pin "1") (pinfunction "P_1") (pintype "passive"))
      (node (ref "R30") (pin "1") (pinfunction "1_1") (pintype "passive"))
    )
    (net (code "55") (name "Net-(IC4A-G)") (class "Default")
      (node (ref "IC4") (pin "5") (pinfunction "G_5") (pintype "input"))
      (node (ref "PAD31") (pin "1") (pinfunction "P_1") (pintype "passive"))
      (node (ref "R31") (pin "1") (pinfunction "1_1") (pintype "passive"))
    )
    (net (code "56") (name "Net-(IC4A-H)") (class "Default")
      (node (ref "IC4") (pin "6") (pinfunction "H_6") (pintype "input"))
      (node (ref "PAD32") (pin "1") (pinfunction "P_1") (pintype "passive"))
      (node (ref "R32") (pin "1") (pinfunction "1_1") (pintype "passive"))
    )
    (net (code "57") (name "Net-(IC4A-SER)") (class "Default")
      (node (ref "IC4") (pin "10") (pinfunction "SER_10") (pintype "input"))
      (node (ref "SERIE3") (pin "1") (pinfunction "P_1") (pintype "passive"))
    )
    (net (code "58") (name "Net-(IC4A-SH{slash}~{LD})") (class "Default")
      (node (ref "IC4") (pin "1") (pinfunction "SH/~{LD}_1") (pintype "input"))
      (node (ref "LOAD3") (pin "1") (pinfunction "P_1") (pintype "passive"))
    )
    (net (code "59") (name "Net-(IC5A-A)") (class "Default")
      (node (ref "IC5") (pin "11") (pinfunction "A_11") (pintype "input"))
      (node (ref "PAD33") (pin "1") (pinfunction "P_1") (pintype "passive"))
      (node (ref "R33") (pin "1") (pinfunction "1_1") (pintype "passive"))
    )
    (net (code "60") (name "Net-(IC5A-B)") (class "Default")
      (node (ref "IC5") (pin "12") (pinfunction "B_12") (pintype "input"))
      (node (ref "PAD34") (pin "1") (pinfunction "P_1") (pintype "passive"))
      (node (ref "R34") (pin "1") (pinfunction "1_1") (pintype "passive"))
    )
    (net (code "61") (name "Net-(IC5A-C)") (class "Default")
      (node (ref "IC5") (pin "13") (pinfunction "C_13") (pintype "input"))
      (node (ref "PAD35") (pin "1") (pinfunction "P_1") (pintype "passive"))
      (node (ref "R35") (pin "1") (pinfunction "1_1") (pintype "passive"))
    )
    (net (code "62") (name "Net-(IC5A-CLK)") (class "Default")
      (node (ref "IC5") (pin "2") (pinfunction "CLK_2") (pintype "input"))
      (node (ref "RELOJ4") (pin "1") (pinfunction "P_1") (pintype "passive"))
    )
    (net (code "63") (name "Net-(IC5A-D)") (class "Default")
      (node (ref "IC5") (pin "14") (pinfunction "D_14") (pintype "input"))
      (node (ref "PAD36") (pin "1") (pinfunction "P_1") (pintype "passive"))
      (node (ref "R36") (pin "1") (pinfunction "1_1") (pintype "passive"))
    )
    (net (code "64") (name "Net-(IC5A-E)") (class "Default")
      (node (ref "IC5") (pin "3") (pinfunction "E_3") (pintype "input"))
      (node (ref "PAD37") (pin "1") (pinfunction "P_1") (pintype "passive"))
      (node (ref "R37") (pin "1") (pinfunction "1_1") (pintype "passive"))
    )
    (net (code "65") (name "Net-(IC5A-F)") (class "Default")
      (node (ref "IC5") (pin "4") (pinfunction "F_4") (pintype "input"))
      (node (ref "PAD38") (pin "1") (pinfunction "P_1") (pintype "passive"))
      (node (ref "R38") (pin "1") (pinfunction "1_1") (pintype "passive"))
    )
    (net (code "66") (name "Net-(IC5A-G)") (class "Default")
      (node (ref "IC5") (pin "5") (pinfunction "G_5") (pintype "input"))
      (node (ref "PAD39") (pin "1") (pinfunction "P_1") (pintype "passive"))
      (node (ref "R39") (pin "1") (pinfunction "1_1") (pintype "passive"))
    )
    (net (code "67") (name "Net-(IC5A-H)") (class "Default")
      (node (ref "IC5") (pin "6") (pinfunction "H_6") (pintype "input"))
      (node (ref "PAD40") (pin "1") (pinfunction "P_1") (pintype "passive"))
      (node (ref "R40") (pin "1") (pinfunction "1_1") (pintype "passive"))
    )
    (net (code "68") (name "Net-(IC5A-SER)") (class "Default")
      (node (ref "IC5") (pin "10") (pinfunction "SER_10") (pintype "input"))
      (node (ref "SERIE4") (pin "1") (pinfunction "P_1") (pintype "passive"))
    )
    (net (code "69") (name "Net-(IC5A-SH{slash}~{LD})") (class "Default")
      (node (ref "IC5") (pin "1") (pinfunction "SH/~{LD}_1") (pintype "input"))
      (node (ref "LOAD4") (pin "1") (pinfunction "P_1") (pintype "passive"))
    )
    (net (code "70") (name "Net-(IC6A-A)") (class "Default")
      (node (ref "IC6") (pin "11") (pinfunction "A_11") (pintype "input"))
      (node (ref "PAD41") (pin "1") (pinfunction "P_1") (pintype "passive"))
      (node (ref "R41") (pin "1") (pinfunction "1_1") (pintype "passive"))
    )
    (net (code "71") (name "Net-(IC6A-B)") (class "Default")
      (node (ref "IC6") (pin "12") (pinfunction "B_12") (pintype "input"))
      (node (ref "PAD42") (pin "1") (pinfunction "P_1") (pintype "passive"))
      (node (ref "R42") (pin "1") (pinfunction "1_1") (pintype "passive"))
    )
    (net (code "72") (name "Net-(IC6A-C)") (class "Default")
      (node (ref "IC6") (pin "13") (pinfunction "C_13") (pintype "input"))
      (node (ref "PAD43") (pin "1") (pinfunction "P_1") (pintype "passive"))
      (node (ref "R43") (pin "1") (pinfunction "1_1") (pintype "passive"))
    )
    (net (code "73") (name "Net-(IC6A-CLK)") (class "Default")
      (node (ref "IC6") (pin "2") (pinfunction "CLK_2") (pintype "input"))
      (node (ref "RELOJ5") (pin "1") (pinfunction "P_1") (pintype "passive"))
    )
    (net (code "74") (name "Net-(IC6A-D)") (class "Default")
      (node (ref "IC6") (pin "14") (pinfunction "D_14") (pintype "input"))
      (node (ref "PAD44") (pin "1") (pinfunction "P_1") (pintype "passive"))
      (node (ref "R44") (pin "1") (pinfunction "1_1") (pintype "passive"))
    )
    (net (code "75") (name "Net-(IC6A-E)") (class "Default")
      (node (ref "IC6") (pin "3") (pinfunction "E_3") (pintype "input"))
      (node (ref "PAD45") (pin "1") (pinfunction "P_1") (pintype "passive"))
      (node (ref "R45") (pin "1") (pinfunction "1_1") (pintype "passive"))
    )
    (net (code "76") (name "Net-(IC6A-F)") (class "Default")
      (node (ref "IC6") (pin "4") (pinfunction "F_4") (pintype "input"))
      (node (ref "PAD46") (pin "1") (pinfunction "P_1") (pintype "passive"))
      (node (ref "R46") (pin "1") (pinfunction "1_1") (pintype "passive"))
    )
    (net (code "77") (name "Net-(IC6A-G)") (class "Default")
      (node (ref "IC6") (pin "5") (pinfunction "G_5") (pintype "input"))
      (node (ref "PAD47") (pin "1") (pinfunction "P_1") (pintype "passive"))
      (node (ref "R47") (pin "1") (pinfunction "1_1") (pintype "passive"))
    )
    (net (code "78") (name "Net-(IC6A-H)") (class "Default")
      (node (ref "IC6") (pin "6") (pinfunction "H_6") (pintype "input"))
      (node (ref "PAD48") (pin "1") (pinfunction "P_1") (pintype "passive"))
      (node (ref "R48") (pin "1") (pinfunction "1_1") (pintype "passive"))
    )
    (net (code "79") (name "Net-(IC6A-SH{slash}~{LD})") (class "Default")
      (node (ref "IC6") (pin "1") (pinfunction "SH/~{LD}_1") (pintype "input"))
      (node (ref "LOAD5") (pin "1") (pinfunction "P_1") (pintype "passive"))
    )
    (net (code "80") (name "unconnected-(IC1A-~{QH}-Pad7)") (class "Default")
      (node (ref "IC1") (pin "7") (pinfunction "~{QH}_7") (pintype "output"))
    )
    (net (code "81") (name "unconnected-(IC2A-~{QH}-Pad7)") (class "Default")
      (node (ref "IC2") (pin "7") (pinfunction "~{QH}_7") (pintype "output"))
    )
    (net (code "82") (name "unconnected-(IC3A-~{QH}-Pad7)") (class "Default")
      (node (ref "IC3") (pin "7") (pinfunction "~{QH}_7") (pintype "output"))
    )
    (net (code "83") (name "unconnected-(IC4A-~{QH}-Pad7)") (class "Default")
      (node (ref "IC4") (pin "7") (pinfunction "~{QH}_7") (pintype "output"))
    )
    (net (code "84") (name "unconnected-(IC5A-~{QH}-Pad7)") (class "Default")
      (node (ref "IC5") (pin "7") (pinfunction "~{QH}_7") (pintype "output"))
    )
    (net (code "85") (name "unconnected-(IC6A-SER-Pad10)") (class "Default")
      (node (ref "IC6") (pin "10") (pinfunction "SER_10") (pintype "input"))
    )
    (net (code "86") (name "unconnected-(IC6A-~{QH}-Pad7)") (class "Default")
      (node (ref "IC6") (pin "7") (pinfunction "~{QH}_7") (pintype "output"))
    )
  )
)
